# M_D_ext_power_8_0_2.net
KiCad netlist of a schematic drawn in EAGLE
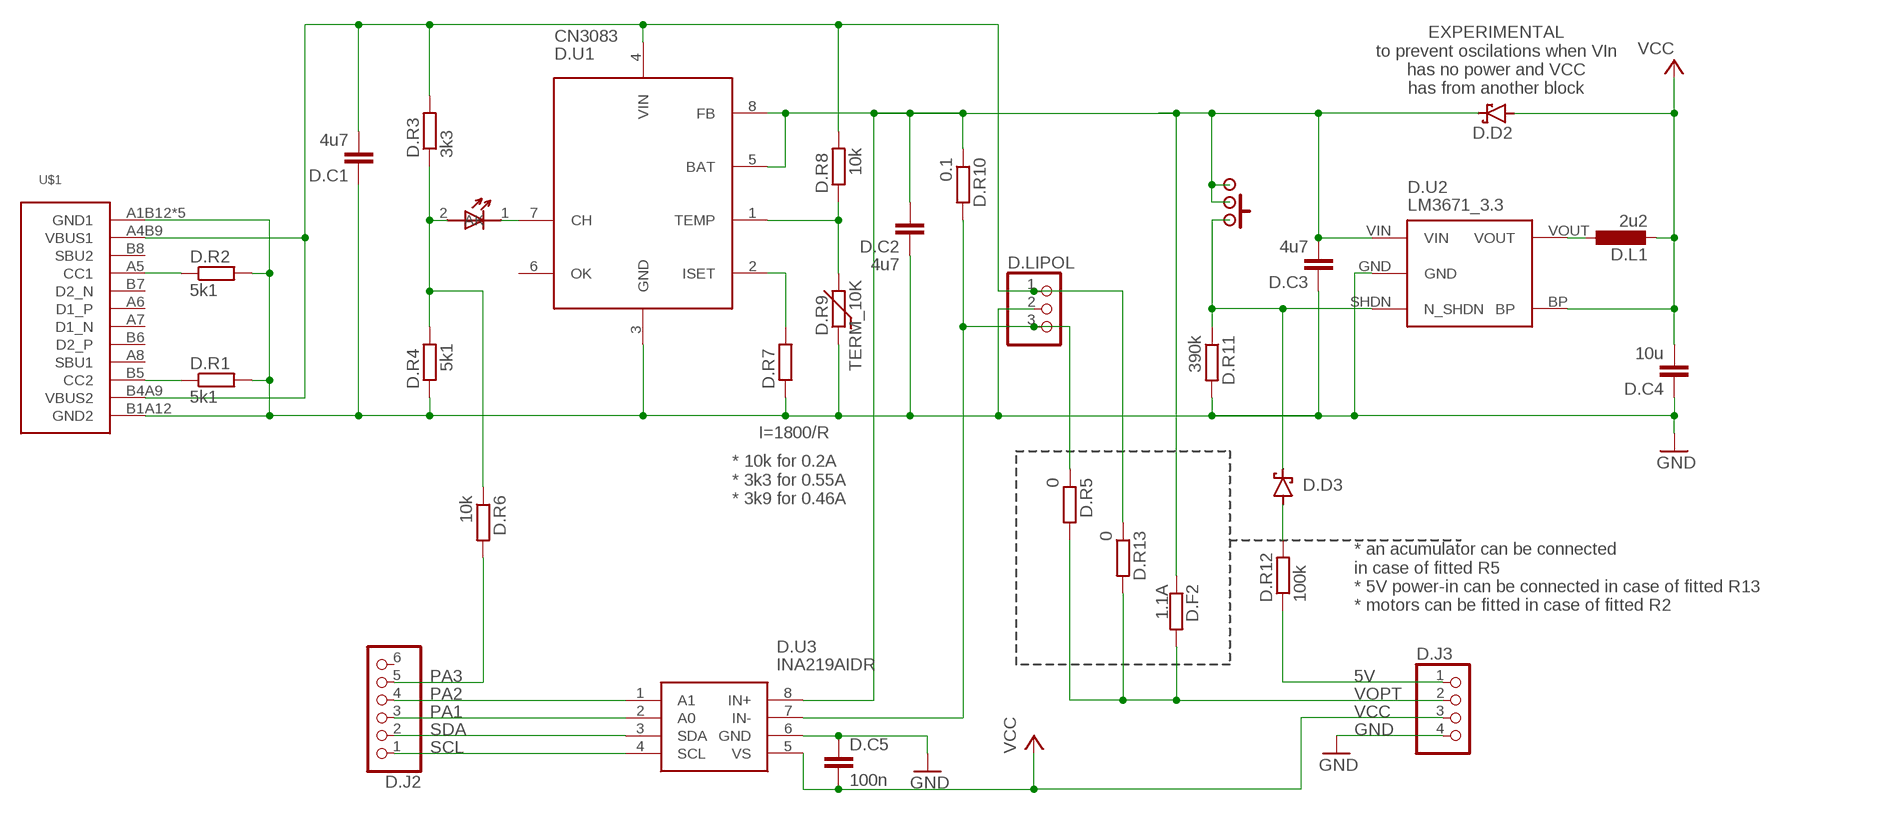
[diagram p0: schematic, sheet 1]

(export (version "E")
  (design (tool "Eeschema 10.0.6"))
  (components
    (comp (ref "D.C1")
      (value "4u7")
      (footprint "eagle-import:C0603")
      (libsource (lib "eagle-import") (part "C-EUC0603"))
    )
    (comp (ref "D.C2")
      (value "4u7")
      (footprint "eagle-import:C0603")
      (libsource (lib "eagle-import") (part "C-EUC0603"))
    )
    (comp (ref "D.C3")
      (value "4u7")
      (footprint "eagle-import:C0603")
      (libsource (lib "eagle-import") (part "C-EUC0603"))
    )
    (comp (ref "D.C4")
      (value "10u")
      (footprint "eagle-import:C0805")
      (libsource (lib "eagle-import") (part "C-EUC0805"))
    )
    (comp (ref "D.C5")
      (value "100n")
      (footprint "eagle-import:C0603")
      (libsource (lib "eagle-import") (part "C-EUC0603"))
    )
    (comp (ref "D.D1")
      (value "LED_1.8")
      (footprint "eagle-import:LED_1.8")
      (libsource (lib "eagle-import") (part "LED_1.8"))
    )
    (comp (ref "D.D2")
      (value "SHOTKY_2.8")
      (footprint "eagle-import:SHOTKY_2.8")
      (libsource (lib "eagle-import") (part "SHOTKY_2.8"))
    )
    (comp (ref "D.D3")
      (value "SHOTKY_2.8")
      (footprint "eagle-import:SHOTKY_2.8")
      (libsource (lib "eagle-import") (part "SHOTKY_2.8"))
    )
    (comp (ref "D.F2")
      (value "1.1A")
      (footprint "eagle-import:R0805")
      (libsource (lib "eagle-import") (part "R-EU_R0805"))
    )
    (comp (ref "D.J2")
      (value "PINHD-1X6")
      (footprint "eagle-import:1X06")
      (libsource (lib "eagle-import") (part "PINHD-1X6"))
    )
    (comp (ref "D.J3")
      (value "PINHD-1X4")
      (footprint "eagle-import:1X04")
      (libsource (lib "eagle-import") (part "PINHD-1X4"))
    )
    (comp (ref "D.L1")
      (value "2u2")
      (footprint "eagle-import:L3230M")
      (libsource (lib "eagle-import") (part "L-EUL3230M"))
    )
    (comp (ref "D.LIPOL")
      (value "PINHEAD-1X3-2")
      (footprint "eagle-import:1X-03-2")
      (libsource (lib "eagle-import") (part "PINHEAD-1X3-2"))
    )
    (comp (ref "D.ON/OFF/RESET")
      (value "SWITCH")
      (footprint "eagle-import:SWITCH")
      (libsource (lib "eagle-import") (part "SWITCH"))
    )
    (comp (ref "D.R1")
      (value "5k1")
      (footprint "eagle-import:R0603")
      (libsource (lib "eagle-import") (part "R-EU_R0603"))
    )
    (comp (ref "D.R2")
      (value "5k1")
      (footprint "eagle-import:R0603")
      (libsource (lib "eagle-import") (part "R-EU_R0603"))
    )
    (comp (ref "D.R3")
      (value "3k3")
      (footprint "eagle-import:R0603")
      (libsource (lib "eagle-import") (part "R-EU_R0603"))
    )
    (comp (ref "D.R4")
      (value "5k1")
      (footprint "eagle-import:R0603")
      (libsource (lib "eagle-import") (part "R-EU_R0603"))
    )
    (comp (ref "D.R5")
      (value "0")
      (footprint "eagle-import:R0603")
      (libsource (lib "eagle-import") (part "R-EU_R0603"))
    )
    (comp (ref "D.R6")
      (value "10k")
      (footprint "eagle-import:R0603")
      (libsource (lib "eagle-import") (part "R-EU_R0603"))
    )
    (comp (ref "D.R7")
      (value "I=1800/R")
      (footprint "eagle-import:R0603")
      (libsource (lib "eagle-import") (part "R-EU_R0603"))
    )
    (comp (ref "D.R8")
      (value "10k")
      (footprint "eagle-import:R0603")
      (libsource (lib "eagle-import") (part "R-EU_R0603"))
    )
    (comp (ref "D.R9")
      (value "TERM_10K")
      (footprint "eagle-import:THERM")
      (libsource (lib "eagle-import") (part "THERM"))
    )
    (comp (ref "D.R10")
      (value "0.1")
      (footprint "eagle-import:R0805")
      (libsource (lib "eagle-import") (part "R-EU_R0805"))
    )
    (comp (ref "D.R11")
      (value "390k")
      (footprint "eagle-import:R0603")
      (libsource (lib "eagle-import") (part "R-EU_R0603"))
    )
    (comp (ref "D.R12")
      (value "100k")
      (footprint "eagle-import:R0603")
      (libsource (lib "eagle-import") (part "R-EU_R0603"))
    )
    (comp (ref "D.R13")
      (value "0")
      (footprint "eagle-import:R0603")
      (libsource (lib "eagle-import") (part "R-EU_R0603"))
    )
    (comp (ref "D.U1")
      (value "CN3083")
      (footprint "eagle-import:SOP8")
      (libsource (lib "eagle-import") (part "CN3083"))
    )
    (comp (ref "D.U2")
      (value "LM3671_3.3")
      (footprint "eagle-import:SOT32-5")
      (libsource (lib "eagle-import") (part "STABILISER_APE8865"))
    )
    (comp (ref "D.U3")
      (value "INA219AIDR")
      (footprint "eagle-import:SOIC127P600X175-8N")
      (fields (field (name "MOUSER_PART_NUMBER") "595-INA219AIDR"))
      (libsource (lib "eagle-import") (part "INA219AIDR"))
    )
    (comp (ref "U$1")
      (value "USB-C")
      (footprint "eagle-import:USB-C")
      (libsource (lib "eagle-import") (part "USB-C"))
    )
  )
  (nets
    (net (code "1") (name "/5V") (class "Default")
      (node (ref "D.C1") (pin "2") (pinfunction "2_2") (pintype "passive"))
      (node (ref "D.LIPOL") (pin "1") (pinfunction "1_1") (pintype "passive"))
      (node (ref "D.R13") (pin "1") (pinfunction "1_1") (pintype "passive"))
      (node (ref "D.R3") (pin "2") (pinfunction "2_2") (pintype "passive"))
      (node (ref "D.R8") (pin "2") (pinfunction "2_2") (pintype "passive"))
      (node (ref "D.U1") (pin "4") (pinfunction "VIN_4") (pintype "bidirectional"))
      (node (ref "U$1") (pin "A4B9") (pinfunction "VBUS1_A4B9") (pintype "bidirectional"))
      (node (ref "U$1") (pin "B4A9") (pinfunction "VBUS2_B4A9") (pintype "bidirectional"))
    )
    (net (code "2") (name "/PA1") (class "Default")
      (node (ref "D.J2") (pin "3") (pinfunction "3_3") (pintype "passive"))
      (node (ref "D.U3") (pin "2") (pinfunction "A0_2") (pintype "bidirectional"))
    )
    (net (code "3") (name "/PA2") (class "Default")
      (node (ref "D.J2") (pin "4") (pinfunction "4_4") (pintype "passive"))
      (node (ref "D.U3") (pin "1") (pinfunction "A1_1") (pintype "bidirectional"))
    )
    (net (code "4") (name "/PA3") (class "Default")
      (node (ref "D.J2") (pin "5") (pinfunction "5_5") (pintype "passive"))
      (node (ref "D.R6") (pin "2") (pinfunction "2_2") (pintype "passive"))
    )
    (net (code "5") (name "/SCL") (class "Default")
      (node (ref "D.J2") (pin "1") (pinfunction "1_1") (pintype "passive"))
      (node (ref "D.U3") (pin "4") (pinfunction "SCL_4") (pintype "bidirectional"))
    )
    (net (code "6") (name "/SDA") (class "Default")
      (node (ref "D.J2") (pin "2") (pinfunction "2_2") (pintype "passive"))
      (node (ref "D.U3") (pin "3") (pinfunction "SDA_3") (pintype "bidirectional"))
    )
    (net (code "7") (name "/VOPT") (class "Default")
      (node (ref "D.F2") (pin "2") (pinfunction "2_2") (pintype "passive"))
      (node (ref "D.J3") (pin "2") (pinfunction "2_2") (pintype "passive"))
      (node (ref "D.R13") (pin "2") (pinfunction "2_2") (pintype "passive"))
      (node (ref "D.R5") (pin "2") (pinfunction "2_2") (pintype "passive"))
    )
    (net (code "8") (name "GND") (class "Default")
      (node (ref "D.C1") (pin "1") (pinfunction "1_1") (pintype "passive"))
      (node (ref "D.C2") (pin "1") (pinfunction "1_1") (pintype "passive"))
      (node (ref "D.C3") (pin "1") (pinfunction "1_1") (pintype "passive"))
      (node (ref "D.C4") (pin "1") (pinfunction "1_1") (pintype "passive"))
      (node (ref "D.C5") (pin "1") (pinfunction "1_1") (pintype "passive"))
      (node (ref "D.J3") (pin "4") (pinfunction "4_4") (pintype "passive"))
      (node (ref "D.LIPOL") (pin "2") (pinfunction "2_2") (pintype "passive"))
      (node (ref "D.R1") (pin "2") (pinfunction "2_2") (pintype "passive"))
      (node (ref "D.R11") (pin "2") (pinfunction "2_2") (pintype "passive"))
      (node (ref "D.R2") (pin "2") (pinfunction "2_2") (pintype "passive"))
      (node (ref "D.R4") (pin "1") (pinfunction "1_1") (pintype "passive"))
      (node (ref "D.R7") (pin "1") (pinfunction "1_1") (pintype "passive"))
      (node (ref "D.R9") (pin "1") (pinfunction "1_1") (pintype "passive"))
      (node (ref "D.U1") (pin "3") (pinfunction "GND_3") (pintype "bidirectional"))
      (node (ref "D.U2") (pin "GND") (pinfunction "GND_GND") (pintype "bidirectional"))
      (node (ref "D.U3") (pin "6") (pinfunction "GND_6") (pintype "bidirectional"))
      (node (ref "U$1") (pin "A1B12") (pinfunction "GND1_A1B12") (pintype "bidirectional"))
      (node (ref "U$1") (pin "B1A12") (pinfunction "GND2_B1A12") (pintype "bidirectional"))
      (node (ref "U$1") (pin "SH1") (pinfunction "GND1_SH1") (pintype "bidirectional"))
      (node (ref "U$1") (pin "SH2") (pinfunction "GND1_SH2") (pintype "bidirectional"))
      (node (ref "U$1") (pin "SH3") (pinfunction "GND1_SH3") (pintype "bidirectional"))
      (node (ref "U$1") (pin "SH4") (pinfunction "GND1_SH4") (pintype "bidirectional"))
    )
    (net (code "9") (name "Net-(D.D1-A)") (class "Default")
      (node (ref "D.D1") (pin "2") (pinfunction "A_2") (pintype "bidirectional"))
      (node (ref "D.R3") (pin "1") (pinfunction "1_1") (pintype "passive"))
      (node (ref "D.R4") (pin "2") (pinfunction "2_2") (pintype "passive"))
      (node (ref "D.R6") (pin "1") (pinfunction "1_1") (pintype "passive"))
    )
    (net (code "10") (name "Net-(D.D1-K)") (class "Default")
      (node (ref "D.D1") (pin "1") (pinfunction "K_1") (pintype "bidirectional"))
      (node (ref "D.U1") (pin "7") (pinfunction "CH_7") (pintype "bidirectional"))
    )
    (net (code "11") (name "Net-(D.D2-C)") (class "Default")
      (node (ref "D.C2") (pin "2") (pinfunction "2_2") (pintype "passive"))
      (node (ref "D.C3") (pin "2") (pinfunction "2_2") (pintype "passive"))
      (node (ref "D.D2") (pin "K") (pinfunction "C_K") (pintype "passive"))
      (node (ref "D.F2") (pin "1") (pinfunction "1_1") (pintype "passive"))
      (node (ref "D.ON/OFF/RESET") (pin "P$2") (pinfunction "P$2_P$2") (pintype "bidirectional"))
      (node (ref "D.ON/OFF/RESET") (pin "P$3") (pinfunction "P$3_P$3") (pintype "bidirectional"))
      (node (ref "D.ON/OFF/RESET") (pin "P$4") (pinfunction "P$3_P$4") (pintype "bidirectional"))
      (node (ref "D.ON/OFF/RESET") (pin "P$6") (pinfunction "P$3_P$6") (pintype "bidirectional"))
      (node (ref "D.R10") (pin "1") (pinfunction "1_1") (pintype "passive"))
      (node (ref "D.U1") (pin "5") (pinfunction "BAT_5") (pintype "bidirectional"))
      (node (ref "D.U1") (pin "8") (pinfunction "FB_8") (pintype "bidirectional"))
      (node (ref "D.U2") (pin "VIN") (pinfunction "VIN_VIN") (pintype "bidirectional"))
      (node (ref "D.U3") (pin "8") (pinfunction "IN+_8") (pintype "bidirectional"))
    )
    (net (code "12") (name "Net-(D.D3-C)") (class "Default")
      (node (ref "D.D3") (pin "K") (pinfunction "C_K") (pintype "passive"))
      (node (ref "D.ON/OFF/RESET") (pin "P$1") (pinfunction "P$1_P$1") (pintype "bidirectional"))
      (node (ref "D.ON/OFF/RESET") (pin "P$5") (pinfunction "P$1_P$5") (pintype "bidirectional"))
      (node (ref "D.ON/OFF/RESET") (pin "P$7") (pinfunction "P$1_P$7") (pintype "bidirectional"))
      (node (ref "D.R11") (pin "1") (pinfunction "1_1") (pintype "passive"))
      (node (ref "D.U2") (pin "SHDN") (pinfunction "N_SHDN_SHDN") (pintype "bidirectional"))
    )
    (net (code "13") (name "Net-(D.D3-PadA)") (class "Default")
      (node (ref "D.D3") (pin "A") (pinfunction "A_A") (pintype "passive"))
      (node (ref "D.R12") (pin "2") (pinfunction "2_2") (pintype "passive"))
    )
    (net (code "14") (name "Net-(D.J3-Pad1)") (class "Default")
      (node (ref "D.J3") (pin "1") (pinfunction "1_1") (pintype "passive"))
      (node (ref "D.R12") (pin "1") (pinfunction "1_1") (pintype "passive"))
    )
    (net (code "15") (name "Net-(D.L1-Pad1)") (class "Default")
      (node (ref "D.L1") (pin "1") (pinfunction "1_1") (pintype "passive"))
      (node (ref "D.U2") (pin "VOUT") (pinfunction "VOUT_VOUT") (pintype "bidirectional"))
    )
    (net (code "16") (name "Net-(D.U1-ISET)") (class "Default")
      (node (ref "D.R7") (pin "2") (pinfunction "2_2") (pintype "passive"))
      (node (ref "D.U1") (pin "2") (pinfunction "ISET_2") (pintype "bidirectional"))
    )
    (net (code "17") (name "Net-(D.U1-TEMP)") (class "Default")
      (node (ref "D.R8") (pin "1") (pinfunction "1_1") (pintype "passive"))
      (node (ref "D.R9") (pin "2") (pinfunction "2_2") (pintype "passive"))
      (node (ref "D.U1") (pin "1") (pinfunction "TEMP_1") (pintype "bidirectional"))
    )
    (net (code "18") (name "Net-(D.U3-IN-)") (class "Default")
      (node (ref "D.LIPOL") (pin "3") (pinfunction "3_3") (pintype "passive"))
      (node (ref "D.R10") (pin "2") (pinfunction "2_2") (pintype "passive"))
      (node (ref "D.R5") (pin "1") (pinfunction "1_1") (pintype "passive"))
      (node (ref "D.U3") (pin "7") (pinfunction "IN-_7") (pintype "bidirectional"))
    )
    (net (code "19") (name "Net-(U$1-CC1)") (class "Default")
      (node (ref "D.R2") (pin "1") (pinfunction "1_1") (pintype "passive"))
      (node (ref "U$1") (pin "A5") (pinfunction "CC1_A5") (pintype "bidirectional"))
    )
    (net (code "20") (name "Net-(U$1-CC2)") (class "Default")
      (node (ref "D.R1") (pin "1") (pinfunction "1_1") (pintype "passive"))
      (node (ref "U$1") (pin "B5") (pinfunction "CC2_B5") (pintype "bidirectional"))
    )
    (net (code "21") (name "VCC") (class "Default")
      (node (ref "D.C4") (pin "2") (pinfunction "2_2") (pintype "passive"))
      (node (ref "D.C5") (pin "2") (pinfunction "2_2") (pintype "passive"))
      (node (ref "D.D2") (pin "A") (pinfunction "A_A") (pintype "passive"))
      (node (ref "D.J3") (pin "3") (pinfunction "3_3") (pintype "passive"))
      (node (ref "D.L1") (pin "2") (pinfunction "2_2") (pintype "passive"))
      (node (ref "D.U2") (pin "BP") (pinfunction "BP_BP") (pintype "bidirectional"))
      (node (ref "D.U3") (pin "5") (pinfunction "VS_5") (pintype "bidirectional"))
    )
    (net (code "22") (name "unconnected-(D.J2-Pad6)") (class "Default")
      (node (ref "D.J2") (pin "6") (pinfunction "6_6") (pintype "passive"))
    )
    (net (code "23") (name "unconnected-(D.U1-OK-Pad6)") (class "Default")
      (node (ref "D.U1") (pin "6") (pinfunction "OK_6") (pintype "bidirectional"))
    )
    (net (code "24") (name "unconnected-(U$1-D1_N-PadA7)") (class "Default")
      (node (ref "U$1") (pin "A7") (pinfunction "D1_N_A7") (pintype "bidirectional"))
    )
    (net (code "25") (name "unconnected-(U$1-D1_P-PadA6)") (class "Default")
      (node (ref "U$1") (pin "A6") (pinfunction "D1_P_A6") (pintype "bidirectional"))
    )
    (net (code "26") (name "unconnected-(U$1-D2_N-PadB7)") (class "Default")
      (node (ref "U$1") (pin "B7") (pinfunction "D2_N_B7") (pintype "bidirectional"))
    )
    (net (code "27") (name "unconnected-(U$1-D2_P-PadB6)") (class "Default")
      (node (ref "U$1") (pin "B6") (pinfunction "D2_P_B6") (pintype "bidirectional"))
    )
    (net (code "28") (name "unconnected-(U$1-SBU1-PadA8)") (class "Default")
      (node (ref "U$1") (pin "A8") (pinfunction "SBU1_A8") (pintype "bidirectional"))
    )
    (net (code "29") (name "unconnected-(U$1-SBU2-PadB8)") (class "Default")
      (node (ref "U$1") (pin "B8") (pinfunction "SBU2_B8") (pintype "bidirectional"))
    )
  )
)
